# Power_Switch.net
KiCad netlist of a schematic drawn in Altium Designer
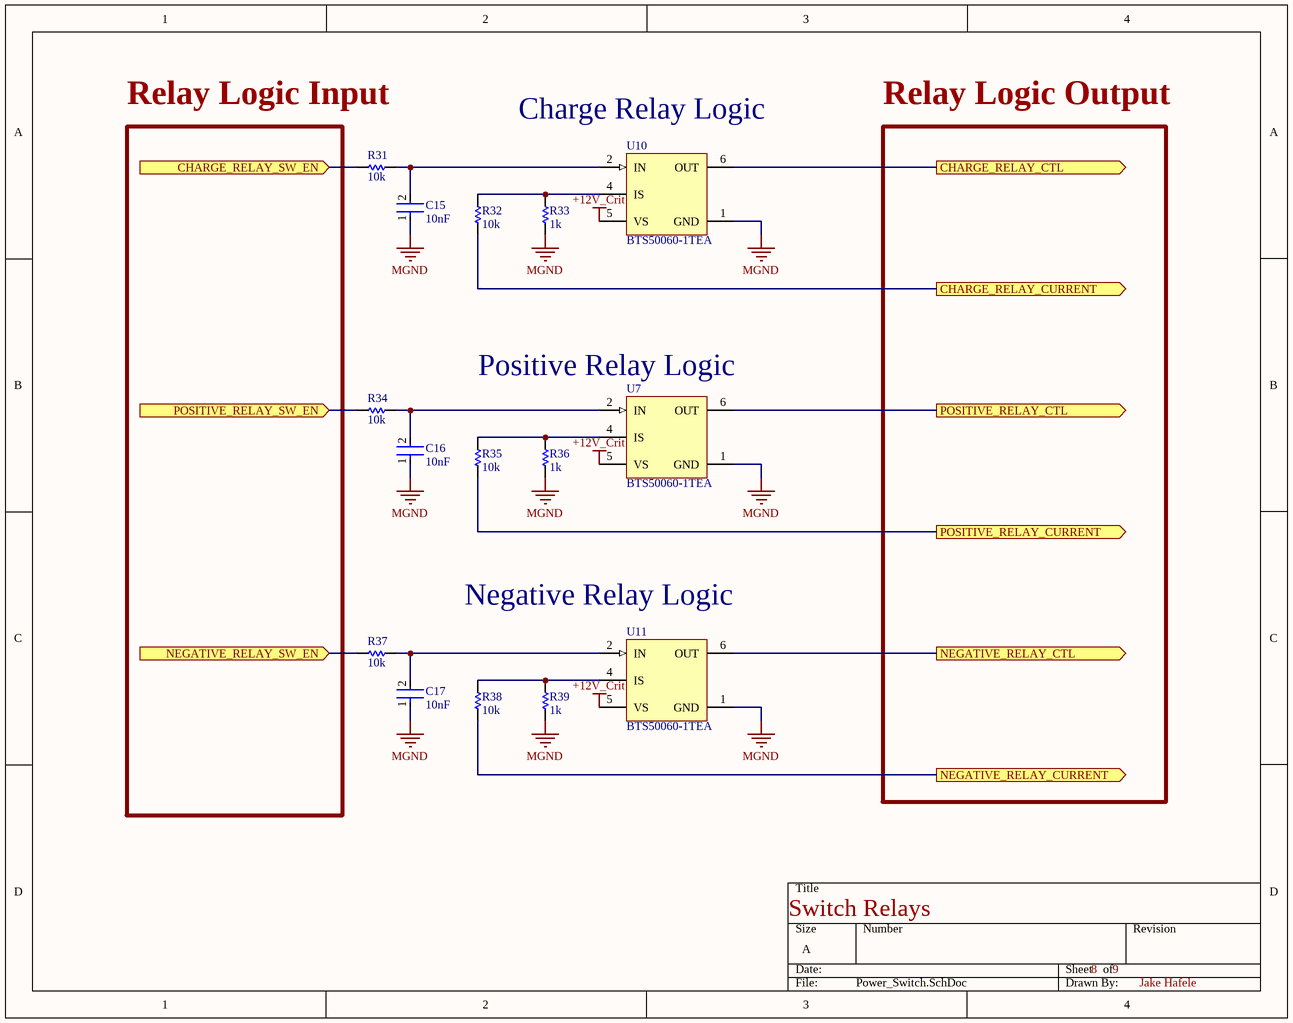
[diagram p0: Power_Switch.SchDoc]

(export (version "E")
  (design (tool "Eeschema 10.0.6"))
  (components
    (comp (ref "C15")
      (value "CGA3E2X8R2A103K080AD")
      (footprint "FP-CGA3E-0_3-0_1-IPC_A")
      (description "Cap Ceramic 10nF 100V X8R 10% Pad SMD 0603 +150°C Automotive T/R")
      (fields (field (name "CAPACITANCE") "10nF") (field (name "TOLERANCE") "10%"))
      (libsource (lib "Altium Content Vault") (part "b4654b650e69147ec39a6b967a45e02"))
    )
    (comp (ref "C16")
      (value "CGA3E2X8R2A103K080AD")
      (footprint "FP-CGA3E-0_3-0_1-IPC_A")
      (description "Cap Ceramic 10nF 100V X8R 10% Pad SMD 0603 +150°C Automotive T/R")
      (fields (field (name "CAPACITANCE") "10nF") (field (name "TOLERANCE") "10%"))
      (libsource (lib "Altium Content Vault") (part "b4654b650e69147ec39a6b967a45e02"))
    )
    (comp (ref "C17")
      (value "CGA3E2X8R2A103K080AD")
      (footprint "FP-CGA3E-0_3-0_1-IPC_A")
      (description "Cap Ceramic 10nF 100V X8R 10% Pad SMD 0603 +150°C Automotive T/R")
      (fields (field (name "CAPACITANCE") "10nF") (field (name "TOLERANCE") "10%"))
      (libsource (lib "Altium Content Vault") (part "b4654b650e69147ec39a6b967a45e02"))
    )
    (comp (ref "R31")
      (value "RES_10k_1%_0603")
      (footprint "R_0603")
      (fields
        (field (name "MANUFACTURER PART NUMBER") "RC0603FR-0710KL")
        (field (name "MANUFACTURER") "Yageo")
        (field (name "DIGIKEY PART NUMBER") "311-10.0KHRCT-ND")
        (field (name "SCHEMATICINFORMATION") "10k")
      )
      (libsource (lib "Resistors") (part "RES_10k_1%_0603"))
    )
    (comp (ref "R32")
      (value "RES_10k_1%_0603")
      (footprint "R_0603")
      (fields
        (field (name "MANUFACTURER PART NUMBER") "RC0603FR-0710KL")
        (field (name "MANUFACTURER") "Yageo")
        (field (name "DIGIKEY PART NUMBER") "311-10.0KHRCT-ND")
        (field (name "SCHEMATICINFORMATION") "10k")
      )
      (libsource (lib "Resistors") (part "RES_10k_1%_0603"))
    )
    (comp (ref "R33")
      (value "RES_1k_1%_0603")
      (footprint "R_0603")
      (fields
        (field (name "MANUFACTURER PART NUMBER") "RC0603FR-071KL")
        (field (name "MANUFACTURER") "Yageo")
        (field (name "DIGIKEY PART NUMBER") "311-1.00KHRCT-ND")
        (field (name "SCHEMATICINFORMATION") "1k")
      )
      (libsource (lib "Resistors") (part "RES_1k_1%_0603"))
    )
    (comp (ref "R34")
      (value "RES_10k_1%_0603")
      (footprint "R_0603")
      (fields
        (field (name "MANUFACTURER PART NUMBER") "RC0603FR-0710KL")
        (field (name "MANUFACTURER") "Yageo")
        (field (name "DIGIKEY PART NUMBER") "311-10.0KHRCT-ND")
        (field (name "SCHEMATICINFORMATION") "10k")
      )
      (libsource (lib "Resistors") (part "RES_10k_1%_0603"))
    )
    (comp (ref "R35")
      (value "RES_10k_1%_0603")
      (footprint "R_0603")
      (fields
        (field (name "MANUFACTURER PART NUMBER") "RC0603FR-0710KL")
        (field (name "MANUFACTURER") "Yageo")
        (field (name "DIGIKEY PART NUMBER") "311-10.0KHRCT-ND")
        (field (name "SCHEMATICINFORMATION") "10k")
      )
      (libsource (lib "Resistors") (part "RES_10k_1%_0603"))
    )
    (comp (ref "R36")
      (value "RES_1k_1%_0603")
      (footprint "R_0603")
      (fields
        (field (name "MANUFACTURER PART NUMBER") "RC0603FR-071KL")
        (field (name "MANUFACTURER") "Yageo")
        (field (name "DIGIKEY PART NUMBER") "311-1.00KHRCT-ND")
        (field (name "SCHEMATICINFORMATION") "1k")
      )
      (libsource (lib "Resistors") (part "RES_1k_1%_0603"))
    )
    (comp (ref "R37")
      (value "RES_10k_1%_0603")
      (footprint "R_0603")
      (fields
        (field (name "MANUFACTURER PART NUMBER") "RC0603FR-0710KL")
        (field (name "MANUFACTURER") "Yageo")
        (field (name "DIGIKEY PART NUMBER") "311-10.0KHRCT-ND")
        (field (name "SCHEMATICINFORMATION") "10k")
      )
      (libsource (lib "Resistors") (part "RES_10k_1%_0603"))
    )
    (comp (ref "R38")
      (value "RES_10k_1%_0603")
      (footprint "R_0603")
      (fields
        (field (name "MANUFACTURER PART NUMBER") "RC0603FR-0710KL")
        (field (name "MANUFACTURER") "Yageo")
        (field (name "DIGIKEY PART NUMBER") "311-10.0KHRCT-ND")
        (field (name "SCHEMATICINFORMATION") "10k")
      )
      (libsource (lib "Resistors") (part "RES_10k_1%_0603"))
    )
    (comp (ref "R39")
      (value "RES_1k_1%_0603")
      (footprint "R_0603")
      (fields
        (field (name "MANUFACTURER PART NUMBER") "RC0603FR-071KL")
        (field (name "MANUFACTURER") "Yageo")
        (field (name "DIGIKEY PART NUMBER") "311-1.00KHRCT-ND")
        (field (name "SCHEMATICINFORMATION") "1k")
      )
      (libsource (lib "Resistors") (part "RES_1k_1%_0603"))
    )
    (comp (ref "U7")
      (value "BTS50060-1TEA")
      (footprint "INF-PG-TO252-5_BTF50060_L")
      (fields (field (name "MANUFACTURER") "Infineon"))
      (libsource (lib "Altium Content Vault") (part "INF-BTX50060-1TEA-PG-TO252-5-11-5"))
    )
    (comp (ref "U10")
      (value "BTS50060-1TEA")
      (footprint "INF-PG-TO252-5_BTF50060_L")
      (fields (field (name "MANUFACTURER") "Infineon"))
      (libsource (lib "Altium Content Vault") (part "INF-BTX50060-1TEA-PG-TO252-5-11-5"))
    )
    (comp (ref "U11")
      (value "BTS50060-1TEA")
      (footprint "INF-PG-TO252-5_BTF50060_L")
      (fields (field (name "MANUFACTURER") "Infineon"))
      (libsource (lib "Altium Content Vault") (part "INF-BTX50060-1TEA-PG-TO252-5-11-5"))
    )
  )
  (nets
    (net (code "1") (name "+12V_Crit") (class "Default")
      (node (ref "U10") (pin "5") (pinfunction "VS_5") (pintype "power_in"))
      (node (ref "U11") (pin "5") (pinfunction "VS_5") (pintype "power_in"))
      (node (ref "U7") (pin "5") (pinfunction "VS_5") (pintype "power_in"))
    )
    (net (code "2") (name "/CHARGE_RELAY_CTL") (class "Default")
      (node (ref "U10") (pin "6") (pinfunction "OUT_6") (pintype "power_in"))
    )
    (net (code "3") (name "/CHARGE_RELAY_CURRENT") (class "Default")
      (node (ref "R32") (pin "1") (pinfunction "1_1") (pintype "passive"))
    )
    (net (code "4") (name "/CHARGE_RELAY_SW_EN") (class "Default")
      (node (ref "R31") (pin "1") (pinfunction "1_1") (pintype "passive"))
    )
    (net (code "5") (name "/NEGATIVE_RELAY_CTL") (class "Default")
      (node (ref "U11") (pin "6") (pinfunction "OUT_6") (pintype "power_in"))
    )
    (net (code "6") (name "/NEGATIVE_RELAY_CURRENT") (class "Default")
      (node (ref "R38") (pin "1") (pinfunction "1_1") (pintype "passive"))
    )
    (net (code "7") (name "/NEGATIVE_RELAY_SW_EN") (class "Default")
      (node (ref "R37") (pin "1") (pinfunction "1_1") (pintype "passive"))
    )
    (net (code "8") (name "/POSITIVE_RELAY_CTL") (class "Default")
      (node (ref "U7") (pin "6") (pinfunction "OUT_6") (pintype "power_in"))
    )
    (net (code "9") (name "/POSITIVE_RELAY_CURRENT") (class "Default")
      (node (ref "R35") (pin "1") (pinfunction "1_1") (pintype "passive"))
    )
    (net (code "10") (name "/POSITIVE_RELAY_SW_EN") (class "Default")
      (node (ref "R34") (pin "1") (pinfunction "1_1") (pintype "passive"))
    )
    (net (code "11") (name "MGND") (class "Default")
      (node (ref "C15") (pin "1") (pinfunction "1_1") (pintype "passive"))
      (node (ref "C16") (pin "1") (pinfunction "1_1") (pintype "passive"))
      (node (ref "C17") (pin "1") (pinfunction "1_1") (pintype "passive"))
      (node (ref "R33") (pin "1") (pinfunction "1_1") (pintype "passive"))
      (node (ref "R36") (pin "1") (pinfunction "1_1") (pintype "passive"))
      (node (ref "R39") (pin "1") (pinfunction "1_1") (pintype "passive"))
      (node (ref "U10") (pin "1") (pinfunction "GND_1") (pintype "power_in"))
      (node (ref "U11") (pin "1") (pinfunction "GND_1") (pintype "power_in"))
      (node (ref "U7") (pin "1") (pinfunction "GND_1") (pintype "power_in"))
    )
    (net (code "12") (name "Net-(U7-IN)") (class "Default")
      (node (ref "C16") (pin "2") (pinfunction "2_2") (pintype "passive"))
      (node (ref "R34") (pin "2") (pinfunction "2_2") (pintype "passive"))
      (node (ref "U7") (pin "2") (pinfunction "IN_2") (pintype "input"))
    )
    (net (code "13") (name "Net-(U7-IS)") (class "Default")
      (node (ref "R35") (pin "2") (pinfunction "2_2") (pintype "passive"))
      (node (ref "R36") (pin "2") (pinfunction "2_2") (pintype "passive"))
      (node (ref "U7") (pin "4") (pinfunction "IS_4") (pintype "tri_state"))
    )
    (net (code "14") (name "Net-(U10-IN)") (class "Default")
      (node (ref "C15") (pin "2") (pinfunction "2_2") (pintype "passive"))
      (node (ref "R31") (pin "2") (pinfunction "2_2") (pintype "passive"))
      (node (ref "U10") (pin "2") (pinfunction "IN_2") (pintype "input"))
    )
    (net (code "15") (name "Net-(U10-IS)") (class "Default")
      (node (ref "R32") (pin "2") (pinfunction "2_2") (pintype "passive"))
      (node (ref "R33") (pin "2") (pinfunction "2_2") (pintype "passive"))
      (node (ref "U10") (pin "4") (pinfunction "IS_4") (pintype "tri_state"))
    )
    (net (code "16") (name "Net-(U11-IN)") (class "Default")
      (node (ref "C17") (pin "2") (pinfunction "2_2") (pintype "passive"))
      (node (ref "R37") (pin "2") (pinfunction "2_2") (pintype "passive"))
      (node (ref "U11") (pin "2") (pinfunction "IN_2") (pintype "input"))
    )
    (net (code "17") (name "Net-(U11-IS)") (class "Default")
      (node (ref "R38") (pin "2") (pinfunction "2_2") (pintype "passive"))
      (node (ref "R39") (pin "2") (pinfunction "2_2") (pintype "passive"))
      (node (ref "U11") (pin "4") (pinfunction "IS_4") (pintype "tri_state"))
    )
  )
)
